# wifiboard.net
KiCad netlist of a schematic drawn in EAGLE
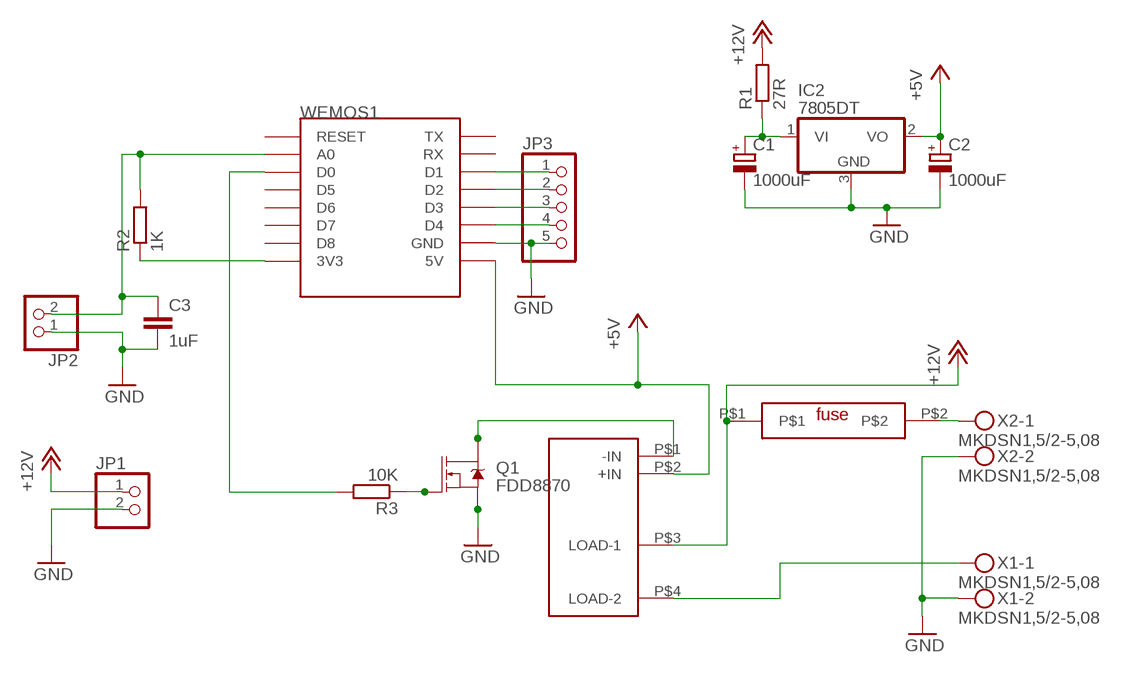
[diagram p0: schematic, sheet 1]

(export (version "E")
  (design (tool "Eeschema 10.0.6"))
  (components
    (comp (ref "C1")
      (value "1000uF")
      (footprint "eagle-import:B45181B")
      (libsource (lib "eagle-import") (part "CPOL-EUB45181B"))
    )
    (comp (ref "C2")
      (value "1000uF")
      (footprint "eagle-import:B45181B")
      (libsource (lib "eagle-import") (part "CPOL-EUB45181B"))
    )
    (comp (ref "C3")
      (value "1uF")
      (footprint "eagle-import:C0805")
      (libsource (lib "eagle-import") (part "C-EUC0805"))
    )
    (comp (ref "IC2")
      (value "7805DT")
      (footprint "eagle-import:TO252")
      (libsource (lib "eagle-import") (part "78DT05"))
    )
    (comp (ref "JP1")
      (value "PINHD-1X2")
      (footprint "eagle-import:1X02")
      (libsource (lib "eagle-import") (part "PINHD-1X2"))
    )
    (comp (ref "JP2")
      (value "PINHD-1X2")
      (footprint "eagle-import:1X02")
      (libsource (lib "eagle-import") (part "PINHD-1X2"))
    )
    (comp (ref "JP3")
      (value "PINHD-1X5")
      (footprint "eagle-import:1X05")
      (libsource (lib "eagle-import") (part "PINHD-1X5"))
    )
    (comp (ref "Q1")
      (value "FDD8870")
      (footprint "eagle-import:DPAK")
      (libsource (lib "eagle-import") (part "MOSFET-NCH-FDD8780"))
    )
    (comp (ref "R1")
      (value "27R")
      (footprint "eagle-import:0207_10")
      (libsource (lib "eagle-import") (part "R-EU_0207/10"))
    )
    (comp (ref "R2")
      (value "1K")
      (footprint "eagle-import:M0805")
      (libsource (lib "eagle-import") (part "R-EU_M0805"))
    )
    (comp (ref "R3")
      (value "10K")
      (footprint "eagle-import:M0805")
      (libsource (lib "eagle-import") (part "R-EU_M0805"))
    )
    (comp (ref "U$1")
      (value "OMRON-G6DS")
      (footprint "eagle-import:OMRON-G6DS-1A-H")
      (libsource (lib "eagle-import") (part "OMRON-G6DS"))
    )
    (comp (ref "U$2")
      (value "FUSE")
      (footprint "eagle-import:FUSE")
      (libsource (lib "eagle-import") (part "FUSE"))
    )
    (comp (ref "WEMOS1")
      (value "WEMOS-D1-MINI")
      (footprint "eagle-import:WEMOS-D1-MINI")
      (libsource (lib "eagle-import") (part "WEMOS-D1-MINI"))
    )
    (comp (ref "X1")
      (value "MKDSN1,5/2-5,08")
      (footprint "eagle-import:MKDSN1,5_2-5,08")
      (libsource (lib "eagle-import") (part "MKDSN1,5/2-5,08"))
    )
    (comp (ref "X2")
      (value "MKDSN1,5/2-5,08")
      (footprint "eagle-import:MKDSN1,5_2-5,08")
      (libsource (lib "eagle-import") (part "MKDSN1,5/2-5,08"))
    )
  )
  (nets
    (net (code "1") (name "+5V") (class "Default")
      (node (ref "C2") (pin "+") (pinfunction "+_+") (pintype "passive"))
      (node (ref "IC2") (pin "2") (pinfunction "VO_2") (pintype "passive"))
      (node (ref "U$1") (pin "P$2") (pinfunction "+IN_P$2") (pintype "input"))
      (node (ref "WEMOS1") (pin "5V") (pinfunction "5V_5V") (pintype "bidirectional"))
    )
    (net (code "2") (name "+12V") (class "Default")
      (node (ref "JP1") (pin "1") (pinfunction "1_1") (pintype "passive"))
      (node (ref "R1") (pin "2") (pinfunction "2_2") (pintype "passive"))
      (node (ref "U$1") (pin "P$3") (pinfunction "LOAD-1_P$3") (pintype "bidirectional"))
      (node (ref "U$2") (pin "P$1") (pinfunction "P$1_P$1") (pintype "bidirectional"))
    )
    (net (code "3") (name "GND") (class "Default")
      (node (ref "C1") (pin "-") (pinfunction "-_-") (pintype "passive"))
      (node (ref "C2") (pin "-") (pinfunction "-_-") (pintype "passive"))
      (node (ref "C3") (pin "2") (pinfunction "2_2") (pintype "passive"))
      (node (ref "IC2") (pin "3") (pinfunction "GND_3") (pintype "passive"))
      (node (ref "JP1") (pin "2") (pinfunction "2_2") (pintype "passive"))
      (node (ref "JP2") (pin "1") (pinfunction "1_1") (pintype "passive"))
      (node (ref "JP3") (pin "5") (pinfunction "5_5") (pintype "passive"))
      (node (ref "Q1") (pin "3") (pinfunction "S_3") (pintype "bidirectional"))
      (node (ref "WEMOS1") (pin "GND") (pinfunction "GND_GND") (pintype "bidirectional"))
      (node (ref "X1") (pin "2") (pinfunction "KL_2") (pintype "passive"))
      (node (ref "X2") (pin "2") (pinfunction "KL_2") (pintype "passive"))
    )
    (net (code "4") (name "Net-(C3-Pad1)") (class "Default")
      (node (ref "C3") (pin "1") (pinfunction "1_1") (pintype "passive"))
      (node (ref "JP2") (pin "2") (pinfunction "2_2") (pintype "passive"))
      (node (ref "R2") (pin "2") (pinfunction "2_2") (pintype "passive"))
      (node (ref "WEMOS1") (pin "A0") (pinfunction "A0_A0") (pintype "bidirectional"))
    )
    (net (code "5") (name "Net-(IC2-VI)") (class "Default")
      (node (ref "C1") (pin "+") (pinfunction "+_+") (pintype "passive"))
      (node (ref "IC2") (pin "1") (pinfunction "VI_1") (pintype "input"))
      (node (ref "R1") (pin "1") (pinfunction "1_1") (pintype "passive"))
    )
    (net (code "6") (name "Net-(JP3-Pad1)") (class "Default")
      (node (ref "JP3") (pin "1") (pinfunction "1_1") (pintype "passive"))
      (node (ref "WEMOS1") (pin "D1") (pinfunction "D1_D1") (pintype "bidirectional"))
    )
    (net (code "7") (name "Net-(JP3-Pad2)") (class "Default")
      (node (ref "JP3") (pin "2") (pinfunction "2_2") (pintype "passive"))
      (node (ref "WEMOS1") (pin "D2") (pinfunction "D2_D2") (pintype "bidirectional"))
    )
    (net (code "8") (name "Net-(JP3-Pad3)") (class "Default")
      (node (ref "JP3") (pin "3") (pinfunction "3_3") (pintype "passive"))
      (node (ref "WEMOS1") (pin "D3") (pinfunction "D3_D3") (pintype "bidirectional"))
    )
    (net (code "9") (name "Net-(JP3-Pad4)") (class "Default")
      (node (ref "JP3") (pin "4") (pinfunction "4_4") (pintype "passive"))
      (node (ref "WEMOS1") (pin "D4") (pinfunction "D4_D4") (pintype "bidirectional"))
    )
    (net (code "10") (name "Net-(Q1-D)") (class "Default")
      (node (ref "Q1") (pin "4") (pinfunction "D_4") (pintype "bidirectional"))
      (node (ref "U$1") (pin "P$1") (pinfunction "-IN_P$1") (pintype "input"))
    )
    (net (code "11") (name "Net-(Q1-G)") (class "Default")
      (node (ref "Q1") (pin "1") (pinfunction "G_1") (pintype "bidirectional"))
      (node (ref "R3") (pin "1") (pinfunction "1_1") (pintype "passive"))
    )
    (net (code "12") (name "Net-(R2-Pad1)") (class "Default")
      (node (ref "R2") (pin "1") (pinfunction "1_1") (pintype "passive"))
      (node (ref "WEMOS1") (pin "3V3") (pinfunction "3V3_3V3") (pintype "bidirectional"))
    )
    (net (code "13") (name "Net-(R3-Pad2)") (class "Default")
      (node (ref "R3") (pin "2") (pinfunction "2_2") (pintype "passive"))
      (node (ref "WEMOS1") (pin "D0") (pinfunction "D0_D0") (pintype "bidirectional"))
    )
    (net (code "14") (name "Net-(U$1-LOAD-2)") (class "Default")
      (node (ref "U$1") (pin "P$4") (pinfunction "LOAD-2_P$4") (pintype "bidirectional"))
      (node (ref "X1") (pin "1") (pinfunction "KL_1") (pintype "passive"))
    )
    (net (code "15") (name "Net-(X2A-KL)") (class "Default")
      (node (ref "U$2") (pin "P$2") (pinfunction "P$2_P$2") (pintype "bidirectional"))
      (node (ref "X2") (pin "1") (pinfunction "KL_1") (pintype "passive"))
    )
    (net (code "16") (name "unconnected-(WEMOS1-PadD5)") (class "Default")
      (node (ref "WEMOS1") (pin "D5") (pinfunction "D5_D5") (pintype "bidirectional"))
    )
    (net (code "17") (name "unconnected-(WEMOS1-PadD6)") (class "Default")
      (node (ref "WEMOS1") (pin "D6") (pinfunction "D6_D6") (pintype "bidirectional"))
    )
    (net (code "18") (name "unconnected-(WEMOS1-PadD7)") (class "Default")
      (node (ref "WEMOS1") (pin "D7") (pinfunction "D7_D7") (pintype "bidirectional"))
    )
    (net (code "19") (name "unconnected-(WEMOS1-PadD8)") (class "Default")
      (node (ref "WEMOS1") (pin "D8") (pinfunction "D8_D8") (pintype "bidirectional"))
    )
    (net (code "20") (name "unconnected-(WEMOS1-PadRESET)") (class "Default")
      (node (ref "WEMOS1") (pin "RESET") (pinfunction "RESET_RESET") (pintype "bidirectional"))
    )
    (net (code "21") (name "unconnected-(WEMOS1-PadRX)") (class "Default")
      (node (ref "WEMOS1") (pin "RX") (pinfunction "RX_RX") (pintype "bidirectional"))
    )
    (net (code "22") (name "unconnected-(WEMOS1-PadTX)") (class "Default")
      (node (ref "WEMOS1") (pin "TX") (pinfunction "TX_TX") (pintype "bidirectional"))
    )
  )
)
